# christmas_card.net
KiCad netlist of a schematic drawn in EAGLE
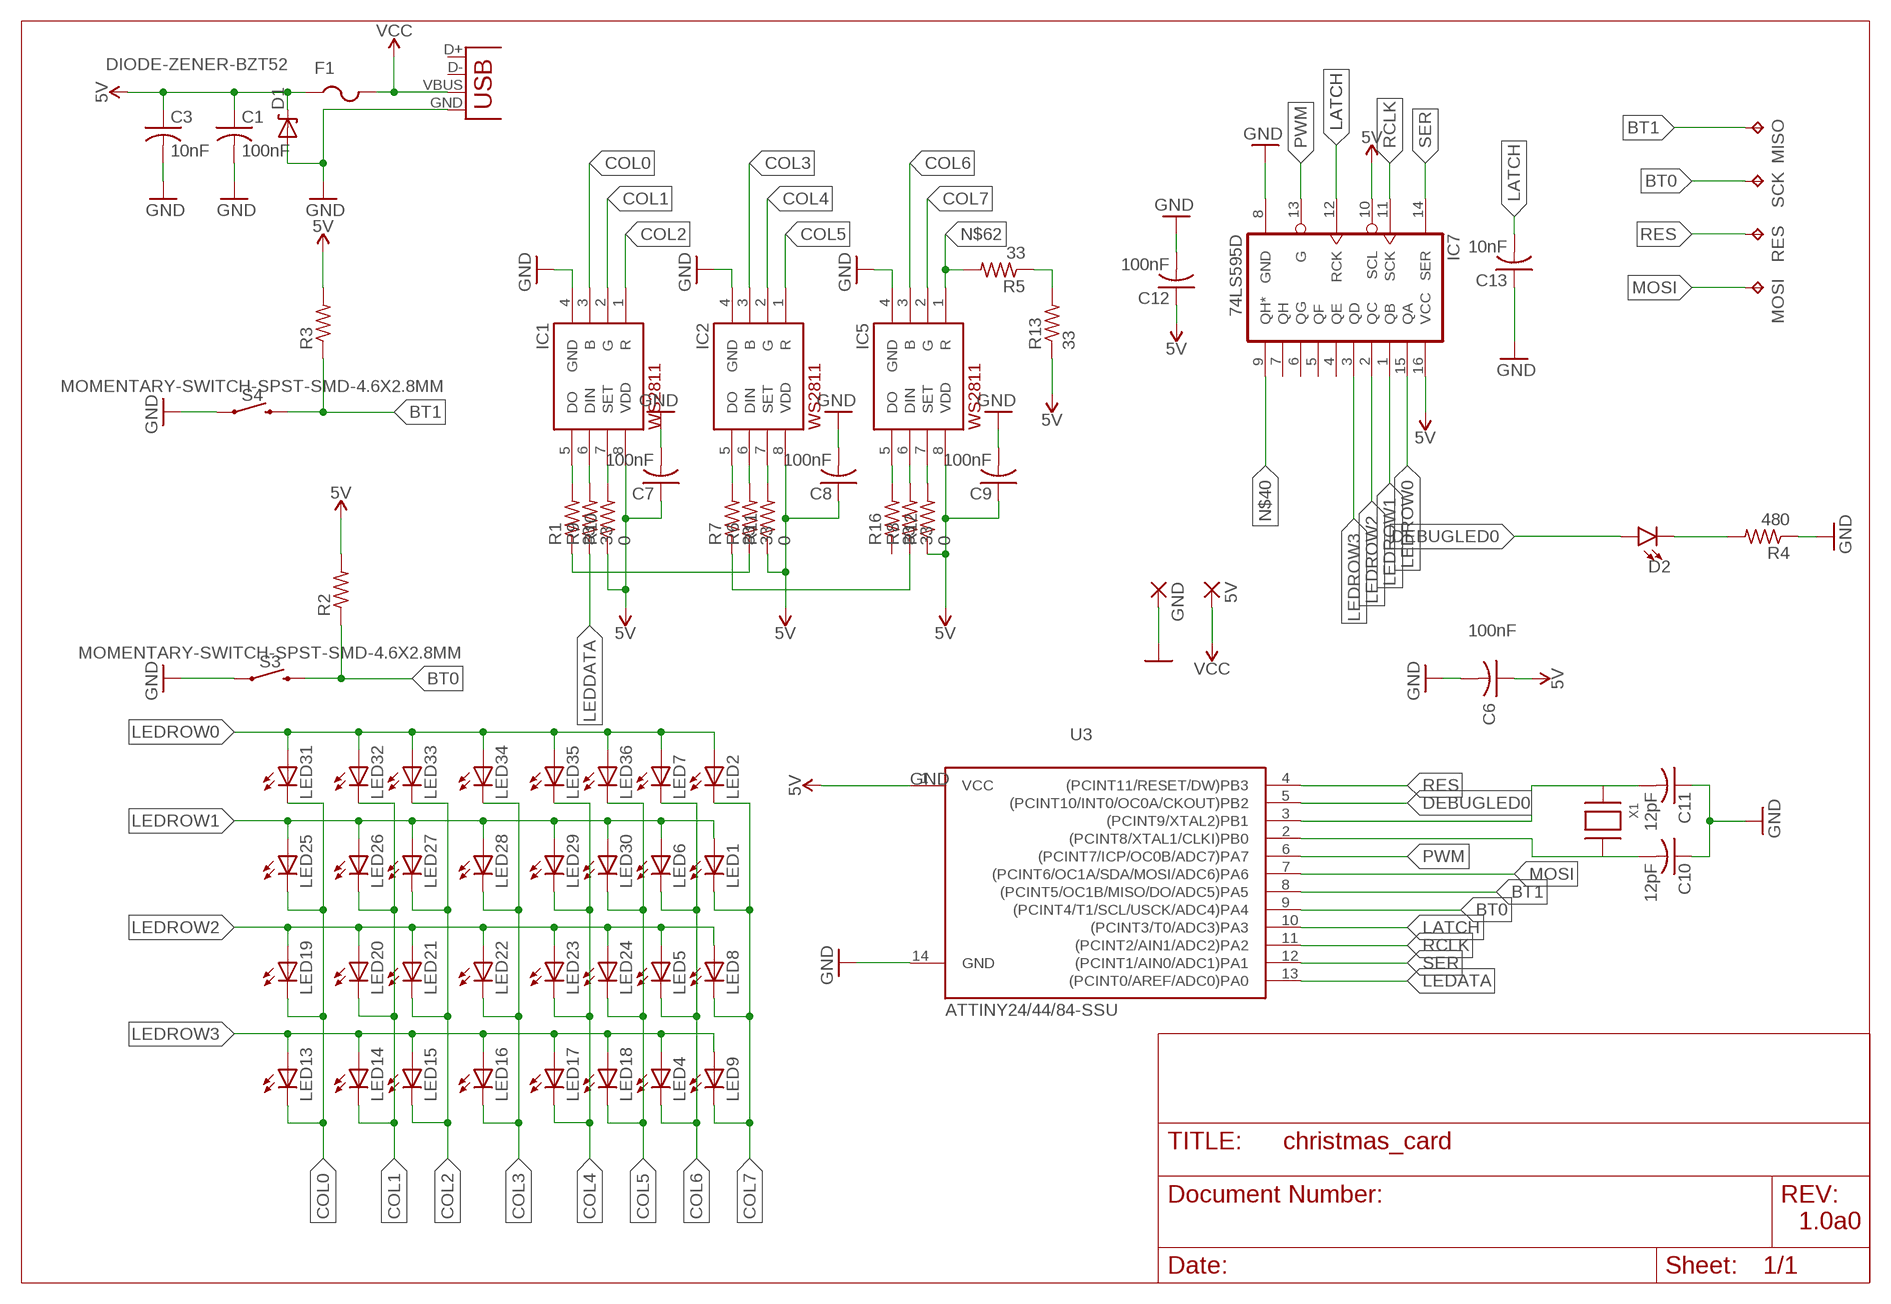
[diagram p0: schematic, sheet 1]

(export (version "E")
  (design (tool "Eeschema 10.0.6"))
  (components
    (comp (ref "5V")
      (value "WIREPADSMD2,54-5,08")
      (footprint "eagle-import:SMD2,54-5,08")
      (libsource (lib "eagle-import") (part "WIREPADSMD2,54-5,08"))
    )
    (comp (ref "C1")
      (value "100nF")
      (footprint "eagle-import:C0603")
      (libsource (lib "eagle-import") (part "C-USC0603"))
    )
    (comp (ref "C3")
      (value "10nF")
      (footprint "eagle-import:C0603")
      (libsource (lib "eagle-import") (part "C-USC0603"))
    )
    (comp (ref "C6")
      (value "100nF")
      (footprint "eagle-import:C0603")
      (libsource (lib "eagle-import") (part "C-USC0603"))
    )
    (comp (ref "C7")
      (value "100nF")
      (footprint "eagle-import:C0603")
      (libsource (lib "eagle-import") (part "C-USC0603"))
    )
    (comp (ref "C8")
      (value "100nF")
      (footprint "eagle-import:C0603")
      (libsource (lib "eagle-import") (part "C-USC0603"))
    )
    (comp (ref "C9")
      (value "100nF")
      (footprint "eagle-import:C0603")
      (libsource (lib "eagle-import") (part "C-USC0603"))
    )
    (comp (ref "C10")
      (value "12pF")
      (footprint "eagle-import:C0603")
      (libsource (lib "eagle-import") (part "C-USC0603"))
    )
    (comp (ref "C11")
      (value "12pF")
      (footprint "eagle-import:C0603")
      (libsource (lib "eagle-import") (part "C-USC0603"))
    )
    (comp (ref "C12")
      (value "100nF")
      (footprint "eagle-import:C0603")
      (libsource (lib "eagle-import") (part "C-USC0603"))
    )
    (comp (ref "C13")
      (value "10nF")
      (footprint "eagle-import:C0603")
      (libsource (lib "eagle-import") (part "C-USC0603"))
    )
    (comp (ref "D1")
      (value "DIODE-ZENER-BZT52")
      (footprint "eagle-import:SOD-323")
      (libsource (lib "eagle-import") (part "DIODE-ZENER-BZT52"))
    )
    (comp (ref "D2")
      (value "LED0603")
      (footprint "eagle-import:LED-0603")
      (libsource (lib "eagle-import") (part "SparkFun-LED_529_LED0603"))
    )
    (comp (ref "F1")
      (value "PTCFUSE-1206")
      (footprint "eagle-import:R1206")
      (libsource (lib "eagle-import") (part "PTCFUSE-1206"))
    )
    (comp (ref "GND")
      (value "WIREPADSMD2,54-5,08")
      (footprint "eagle-import:SMD2,54-5,08")
      (libsource (lib "eagle-import") (part "WIREPADSMD2,54-5,08"))
    )
    (comp (ref "IC1")
      (value "WS2811-SOP8")
      (footprint "eagle-import:SO08-SKINNYPADS")
      (libsource (lib "eagle-import") (part "WS2811-SOP8"))
    )
    (comp (ref "IC2")
      (value "WS2811-SOP8")
      (footprint "eagle-import:SO08-SKINNYPADS")
      (libsource (lib "eagle-import") (part "WS2811-SOP8"))
    )
    (comp (ref "IC5")
      (value "WS2811-SOP8")
      (footprint "eagle-import:SO08-SKINNYPADS")
      (libsource (lib "eagle-import") (part "WS2811-SOP8"))
    )
    (comp (ref "IC7")
      (value "74LS595D")
      (footprint "eagle-import:SO16")
      (fields (field (name "SPICEPREFIX") "X"))
      (libsource (lib "eagle-import") (part "74595DLS"))
    )
    (comp (ref "LED1")
      (value "LED1206")
      (footprint "eagle-import:LED-1206")
      (libsource (lib "eagle-import") (part "LED1206"))
    )
    (comp (ref "LED2")
      (value "LED1206")
      (footprint "eagle-import:LED-1206")
      (libsource (lib "eagle-import") (part "LED1206"))
    )
    (comp (ref "LED4")
      (value "LED1206")
      (footprint "eagle-import:LED-1206")
      (libsource (lib "eagle-import") (part "LED1206"))
    )
    (comp (ref "LED5")
      (value "LED1206")
      (footprint "eagle-import:LED-1206")
      (libsource (lib "eagle-import") (part "LED1206"))
    )
    (comp (ref "LED6")
      (value "LED1206")
      (footprint "eagle-import:LED-1206")
      (libsource (lib "eagle-import") (part "LED1206"))
    )
    (comp (ref "LED7")
      (value "LED1206")
      (footprint "eagle-import:LED-1206")
      (libsource (lib "eagle-import") (part "LED1206"))
    )
    (comp (ref "LED8")
      (value "LED1206")
      (footprint "eagle-import:LED-1206")
      (libsource (lib "eagle-import") (part "LED1206"))
    )
    (comp (ref "LED9")
      (value "LED1206")
      (footprint "eagle-import:LED-1206")
      (libsource (lib "eagle-import") (part "LED1206"))
    )
    (comp (ref "LED13")
      (value "LED1206")
      (footprint "eagle-import:LED-1206")
      (libsource (lib "eagle-import") (part "LED1206"))
    )
    (comp (ref "LED14")
      (value "LED1206")
      (footprint "eagle-import:LED-1206")
      (libsource (lib "eagle-import") (part "LED1206"))
    )
    (comp (ref "LED15")
      (value "LED1206")
      (footprint "eagle-import:LED-1206")
      (libsource (lib "eagle-import") (part "LED1206"))
    )
    (comp (ref "LED16")
      (value "LED1206")
      (footprint "eagle-import:LED-1206")
      (libsource (lib "eagle-import") (part "LED1206"))
    )
    (comp (ref "LED17")
      (value "LED1206")
      (footprint "eagle-import:LED-1206")
      (libsource (lib "eagle-import") (part "LED1206"))
    )
    (comp (ref "LED18")
      (value "LED1206")
      (footprint "eagle-import:LED-1206")
      (libsource (lib "eagle-import") (part "LED1206"))
    )
    (comp (ref "LED19")
      (value "LED1206")
      (footprint "eagle-import:LED-1206")
      (libsource (lib "eagle-import") (part "LED1206"))
    )
    (comp (ref "LED20")
      (value "LED1206")
      (footprint "eagle-import:LED-1206")
      (libsource (lib "eagle-import") (part "LED1206"))
    )
    (comp (ref "LED21")
      (value "LED1206")
      (footprint "eagle-import:LED-1206")
      (libsource (lib "eagle-import") (part "LED1206"))
    )
    (comp (ref "LED22")
      (value "LED1206")
      (footprint "eagle-import:LED-1206")
      (libsource (lib "eagle-import") (part "LED1206"))
    )
    (comp (ref "LED23")
      (value "LED1206")
      (footprint "eagle-import:LED-1206")
      (libsource (lib "eagle-import") (part "LED1206"))
    )
    (comp (ref "LED24")
      (value "LED1206")
      (footprint "eagle-import:LED-1206")
      (libsource (lib "eagle-import") (part "LED1206"))
    )
    (comp (ref "LED25")
      (value "LED1206")
      (footprint "eagle-import:LED-1206")
      (libsource (lib "eagle-import") (part "LED1206"))
    )
    (comp (ref "LED26")
      (value "LED1206")
      (footprint "eagle-import:LED-1206")
      (libsource (lib "eagle-import") (part "LED1206"))
    )
    (comp (ref "LED27")
      (value "LED1206")
      (footprint "eagle-import:LED-1206")
      (libsource (lib "eagle-import") (part "LED1206"))
    )
    (comp (ref "LED28")
      (value "LED1206")
      (footprint "eagle-import:LED-1206")
      (libsource (lib "eagle-import") (part "LED1206"))
    )
    (comp (ref "LED29")
      (value "LED1206")
      (footprint "eagle-import:LED-1206")
      (libsource (lib "eagle-import") (part "LED1206"))
    )
    (comp (ref "LED30")
      (value "LED1206")
      (footprint "eagle-import:LED-1206")
      (libsource (lib "eagle-import") (part "LED1206"))
    )
    (comp (ref "LED31")
      (value "LED1206")
      (footprint "eagle-import:LED-1206")
      (libsource (lib "eagle-import") (part "LED1206"))
    )
    (comp (ref "LED32")
      (value "LED1206")
      (footprint "eagle-import:LED-1206")
      (libsource (lib "eagle-import") (part "LED1206"))
    )
    (comp (ref "LED33")
      (value "LED1206")
      (footprint "eagle-import:LED-1206")
      (libsource (lib "eagle-import") (part "LED1206"))
    )
    (comp (ref "LED34")
      (value "LED1206")
      (footprint "eagle-import:LED-1206")
      (libsource (lib "eagle-import") (part "LED1206"))
    )
    (comp (ref "LED35")
      (value "LED1206")
      (footprint "eagle-import:LED-1206")
      (libsource (lib "eagle-import") (part "LED1206"))
    )
    (comp (ref "LED36")
      (value "LED1206")
      (footprint "eagle-import:LED-1206")
      (libsource (lib "eagle-import") (part "LED1206"))
    )
    (comp (ref "MISO")
      (value "TPB1,27")
      (footprint "eagle-import:B1,27")
      (libsource (lib "eagle-import") (part "TPB1,27"))
    )
    (comp (ref "MOSI")
      (value "TPB1,27")
      (footprint "eagle-import:B1,27")
      (libsource (lib "eagle-import") (part "TPB1,27"))
    )
    (comp (ref "R1")
      (value "33")
      (footprint "eagle-import:R0603")
      (libsource (lib "eagle-import") (part "R-US_R0603"))
    )
    (comp (ref "R2")
      (value "R-US_R0603")
      (footprint "eagle-import:R0603")
      (libsource (lib "eagle-import") (part "R-US_R0603"))
    )
    (comp (ref "R3")
      (value "R-US_R0603")
      (footprint "eagle-import:R0603")
      (libsource (lib "eagle-import") (part "R-US_R0603"))
    )
    (comp (ref "R4")
      (value "480")
      (footprint "eagle-import:R0603")
      (libsource (lib "eagle-import") (part "R-US_R0603"))
    )
    (comp (ref "R5")
      (value "33")
      (footprint "eagle-import:R0603")
      (libsource (lib "eagle-import") (part "R-US_R0603"))
    )
    (comp (ref "R6")
      (value "33")
      (footprint "eagle-import:R0603")
      (libsource (lib "eagle-import") (part "R-US_R0603"))
    )
    (comp (ref "R7")
      (value "33")
      (footprint "eagle-import:R0603")
      (libsource (lib "eagle-import") (part "R-US_R0603"))
    )
    (comp (ref "R8")
      (value "33")
      (footprint "eagle-import:R0603")
      (libsource (lib "eagle-import") (part "R-US_R0603"))
    )
    (comp (ref "R9")
      (value "33")
      (footprint "eagle-import:R0603")
      (libsource (lib "eagle-import") (part "R-US_R0603"))
    )
    (comp (ref "R10")
      (value "0")
      (footprint "eagle-import:R0603")
      (libsource (lib "eagle-import") (part "R-US_R0603"))
    )
    (comp (ref "R11")
      (value "0")
      (footprint "eagle-import:R0603")
      (libsource (lib "eagle-import") (part "R-US_R0603"))
    )
    (comp (ref "R12")
      (value "0")
      (footprint "eagle-import:R0603")
      (libsource (lib "eagle-import") (part "R-US_R0603"))
    )
    (comp (ref "R13")
      (value "33")
      (footprint "eagle-import:R0603")
      (libsource (lib "eagle-import") (part "R-US_R0603"))
    )
    (comp (ref "R16")
      (value "33")
      (footprint "eagle-import:R0603")
      (libsource (lib "eagle-import") (part "R-US_R0603"))
    )
    (comp (ref "RES")
      (value "TPB1,27")
      (footprint "eagle-import:B1,27")
      (libsource (lib "eagle-import") (part "TPB1,27"))
    )
    (comp (ref "S3")
      (value "MOMENTARY-SWITCH-SPST-SMD-4.6X2.8MM")
      (footprint "eagle-import:TACTILE_SWITCH_SMD_4.6X2.8MM")
      (libsource (lib "eagle-import") (part "MOMENTARY-SWITCH-SPST-SMD-4.6X2.8MM"))
    )
    (comp (ref "S4")
      (value "MOMENTARY-SWITCH-SPST-SMD-4.6X2.8MM")
      (footprint "eagle-import:TACTILE_SWITCH_SMD_4.6X2.8MM")
      (libsource (lib "eagle-import") (part "MOMENTARY-SWITCH-SPST-SMD-4.6X2.8MM"))
    )
    (comp (ref "SCK")
      (value "TPB1,27")
      (footprint "eagle-import:B1,27")
      (libsource (lib "eagle-import") (part "TPB1,27"))
    )
    (comp (ref "U3")
      (value "ATTINY24/44/84-SSU")
      (footprint "eagle-import:SOIC14N")
      (libsource (lib "eagle-import") (part "ATTINY24/44/84-SSU"))
    )
    (comp (ref "X1")
      (value "XTALNX5032")
      (footprint "eagle-import:NX5032")
      (libsource (lib "eagle-import") (part "XTALNX5032"))
    )
    (comp (ref "X2")
      (value "USB-MICROB")
      (footprint "eagle-import:USB-MICROB")
      (libsource (lib "eagle-import") (part "USB-MICROB"))
    )
  )
  (nets
    (net (code "1") (name "5V") (class "Default")
      (node (ref "C1") (pin "1") (pinfunction "1_1") (pintype "passive"))
      (node (ref "C12") (pin "1") (pinfunction "1_1") (pintype "passive"))
      (node (ref "C3") (pin "1") (pinfunction "1_1") (pintype "passive"))
      (node (ref "C6") (pin "1") (pinfunction "1_1") (pintype "passive"))
      (node (ref "C7") (pin "1") (pinfunction "1_1") (pintype "passive"))
      (node (ref "C8") (pin "1") (pinfunction "1_1") (pintype "passive"))
      (node (ref "C9") (pin "1") (pinfunction "1_1") (pintype "passive"))
      (node (ref "D1") (pin "1") (pinfunction "C_1") (pintype "passive"))
      (node (ref "F1") (pin "1") (pinfunction "1_1") (pintype "passive"))
      (node (ref "IC1") (pin "8") (pinfunction "VDD_8") (pintype "power_in"))
      (node (ref "IC2") (pin "8") (pinfunction "VDD_8") (pintype "power_in"))
      (node (ref "IC5") (pin "8") (pinfunction "VDD_8") (pintype "power_in"))
      (node (ref "IC7") (pin "10") (pinfunction "SCL_10") (pintype "input"))
      (node (ref "IC7") (pin "16") (pinfunction "VCC_16") (pintype "power_in"))
      (node (ref "R10") (pin "1") (pinfunction "1_1") (pintype "passive"))
      (node (ref "R11") (pin "1") (pinfunction "1_1") (pintype "passive"))
      (node (ref "R12") (pin "1") (pinfunction "1_1") (pintype "passive"))
      (node (ref "R13") (pin "1") (pinfunction "1_1") (pintype "passive"))
      (node (ref "R2") (pin "2") (pinfunction "2_2") (pintype "passive"))
      (node (ref "R3") (pin "2") (pinfunction "2_2") (pintype "passive"))
      (node (ref "U3") (pin "1") (pinfunction "VCC_1") (pintype "bidirectional"))
    )
    (net (code "2") (name "BT0") (class "Default")
      (node (ref "R2") (pin "1") (pinfunction "1_1") (pintype "passive"))
      (node (ref "S3") (pin "3") (pinfunction "2_3") (pintype "passive"))
      (node (ref "S3") (pin "4") (pinfunction "2_4") (pintype "passive"))
      (node (ref "SCK") (pin "TP") (pinfunction "TP_TP") (pintype "input"))
      (node (ref "U3") (pin "9") (pinfunction "(PCINT4/T1/SCL/USCK/ADC4)PA4_9") (pintype "bidirectional"))
    )
    (net (code "3") (name "BT1") (class "Default")
      (node (ref "MISO") (pin "TP") (pinfunction "TP_TP") (pintype "input"))
      (node (ref "R3") (pin "1") (pinfunction "1_1") (pintype "passive"))
      (node (ref "S4") (pin "3") (pinfunction "2_3") (pintype "passive"))
      (node (ref "S4") (pin "4") (pinfunction "2_4") (pintype "passive"))
      (node (ref "U3") (pin "8") (pinfunction "(PCINT5/OC1B/MISO/DO/ADC5)PA5_8") (pintype "bidirectional"))
    )
    (net (code "4") (name "COL0") (class "Default")
      (node (ref "IC1") (pin "3") (pinfunction "B_3") (pintype "open_collector"))
      (node (ref "LED13") (pin "C") (pinfunction "C_C") (pintype "passive"))
      (node (ref "LED19") (pin "C") (pinfunction "C_C") (pintype "passive"))
      (node (ref "LED25") (pin "C") (pinfunction "C_C") (pintype "passive"))
      (node (ref "LED31") (pin "C") (pinfunction "C_C") (pintype "passive"))
    )
    (net (code "5") (name "COL1") (class "Default")
      (node (ref "IC1") (pin "2") (pinfunction "G_2") (pintype "open_collector"))
      (node (ref "LED14") (pin "C") (pinfunction "C_C") (pintype "passive"))
      (node (ref "LED20") (pin "C") (pinfunction "C_C") (pintype "passive"))
      (node (ref "LED26") (pin "C") (pinfunction "C_C") (pintype "passive"))
      (node (ref "LED32") (pin "C") (pinfunction "C_C") (pintype "passive"))
    )
    (net (code "6") (name "COL2") (class "Default")
      (node (ref "IC1") (pin "1") (pinfunction "R_1") (pintype "open_collector"))
      (node (ref "LED15") (pin "C") (pinfunction "C_C") (pintype "passive"))
      (node (ref "LED21") (pin "C") (pinfunction "C_C") (pintype "passive"))
      (node (ref "LED27") (pin "C") (pinfunction "C_C") (pintype "passive"))
      (node (ref "LED33") (pin "C") (pinfunction "C_C") (pintype "passive"))
    )
    (net (code "7") (name "COL3") (class "Default")
      (node (ref "IC2") (pin "3") (pinfunction "B_3") (pintype "open_collector"))
      (node (ref "LED16") (pin "C") (pinfunction "C_C") (pintype "passive"))
      (node (ref "LED22") (pin "C") (pinfunction "C_C") (pintype "passive"))
      (node (ref "LED28") (pin "C") (pinfunction "C_C") (pintype "passive"))
      (node (ref "LED34") (pin "C") (pinfunction "C_C") (pintype "passive"))
    )
    (net (code "8") (name "COL4") (class "Default")
      (node (ref "IC2") (pin "2") (pinfunction "G_2") (pintype "open_collector"))
      (node (ref "LED17") (pin "C") (pinfunction "C_C") (pintype "passive"))
      (node (ref "LED23") (pin "C") (pinfunction "C_C") (pintype "passive"))
      (node (ref "LED29") (pin "C") (pinfunction "C_C") (pintype "passive"))
      (node (ref "LED35") (pin "C") (pinfunction "C_C") (pintype "passive"))
    )
    (net (code "9") (name "COL5") (class "Default")
      (node (ref "IC2") (pin "1") (pinfunction "R_1") (pintype "open_collector"))
      (node (ref "LED18") (pin "C") (pinfunction "C_C") (pintype "passive"))
      (node (ref "LED24") (pin "C") (pinfunction "C_C") (pintype "passive"))
      (node (ref "LED30") (pin "C") (pinfunction "C_C") (pintype "passive"))
      (node (ref "LED36") (pin "C") (pinfunction "C_C") (pintype "passive"))
    )
    (net (code "10") (name "COL6") (class "Default")
      (node (ref "IC5") (pin "3") (pinfunction "B_3") (pintype "open_collector"))
      (node (ref "LED4") (pin "C") (pinfunction "C_C") (pintype "passive"))
      (node (ref "LED5") (pin "C") (pinfunction "C_C") (pintype "passive"))
      (node (ref "LED6") (pin "C") (pinfunction "C_C") (pintype "passive"))
      (node (ref "LED7") (pin "C") (pinfunction "C_C") (pintype "passive"))
    )
    (net (code "11") (name "COL7") (class "Default")
      (node (ref "IC5") (pin "2") (pinfunction "G_2") (pintype "open_collector"))
      (node (ref "LED1") (pin "C") (pinfunction "C_C") (pintype "passive"))
      (node (ref "LED2") (pin "C") (pinfunction "C_C") (pintype "passive"))
      (node (ref "LED8") (pin "C") (pinfunction "C_C") (pintype "passive"))
      (node (ref "LED9") (pin "C") (pinfunction "C_C") (pintype "passive"))
    )
    (net (code "12") (name "DEBUGLED0") (class "Default")
      (node (ref "D2") (pin "A") (pinfunction "A_A") (pintype "passive"))
      (node (ref "U3") (pin "5") (pinfunction "(PCINT10/INT0/OC0A/CKOUT)PB2_5") (pintype "bidirectional"))
    )
    (net (code "13") (name "GND") (class "Default")
      (node (ref "C1") (pin "2") (pinfunction "2_2") (pintype "passive"))
      (node (ref "C10") (pin "1") (pinfunction "1_1") (pintype "passive"))
      (node (ref "C11") (pin "1") (pinfunction "1_1") (pintype "passive"))
      (node (ref "C12") (pin "2") (pinfunction "2_2") (pintype "passive"))
      (node (ref "C13") (pin "1") (pinfunction "1_1") (pintype "passive"))
      (node (ref "C3") (pin "2") (pinfunction "2_2") (pintype "passive"))
      (node (ref "C6") (pin "2") (pinfunction "2_2") (pintype "passive"))
      (node (ref "C7") (pin "2") (pinfunction "2_2") (pintype "passive"))
      (node (ref "C8") (pin "2") (pinfunction "2_2") (pintype "passive"))
      (node (ref "C9") (pin "2") (pinfunction "2_2") (pintype "passive"))
      (node (ref "D1") (pin "2") (pinfunction "A_2") (pintype "passive"))
      (node (ref "GND") (pin "1") (pinfunction "P_1") (pintype "passive"))
      (node (ref "IC1") (pin "4") (pinfunction "GND_4") (pintype "power_in"))
      (node (ref "IC2") (pin "4") (pinfunction "GND_4") (pintype "power_in"))
      (node (ref "IC5") (pin "4") (pinfunction "GND_4") (pintype "power_in"))
      (node (ref "IC7") (pin "8") (pinfunction "GND_8") (pintype "power_in"))
      (node (ref "R4") (pin "1") (pinfunction "1_1") (pintype "passive"))
      (node (ref "S3") (pin "1") (pinfunction "1_1") (pintype "passive"))
      (node (ref "S3") (pin "2") (pinfunction "1_2") (pintype "passive"))
      (node (ref "S4") (pin "1") (pinfunction "1_1") (pintype "passive"))
      (node (ref "S4") (pin "2") (pinfunction "1_2") (pintype "passive"))
      (node (ref "U3") (pin "14") (pinfunction "GND_14") (pintype "bidirectional"))
      (node (ref "X2") (pin "GND") (pinfunction "GND_GND") (pintype "bidirectional"))
    )
    (net (code "14") (name "LATCH") (class "Default")
      (node (ref "C13") (pin "2") (pinfunction "2_2") (pintype "passive"))
      (node (ref "IC7") (pin "12") (pinfunction "RCK_12") (pintype "input"))
      (node (ref "U3") (pin "10") (pinfunction "(PCINT3/T0/ADC3)PA3_10") (pintype "bidirectional"))
    )
    (net (code "15") (name "LEDATA") (class "Default")
      (node (ref "U3") (pin "13") (pinfunction "(PCINT0/AREF/ADC0)PA0_13") (pintype "bidirectional"))
    )
    (net (code "16") (name "LEDDATA") (class "Default")
      (node (ref "R9") (pin "1") (pinfunction "1_1") (pintype "passive"))
    )
    (net (code "17") (name "LEDROW0") (class "Default")
      (node (ref "IC7") (pin "15") (pinfunction "QA_15") (pintype "tri_state"))
      (node (ref "LED2") (pin "A") (pinfunction "A_A") (pintype "passive"))
      (node (ref "LED31") (pin "A") (pinfunction "A_A") (pintype "passive"))
      (node (ref "LED32") (pin "A") (pinfunction "A_A") (pintype "passive"))
      (node (ref "LED33") (pin "A") (pinfunction "A_A") (pintype "passive"))
      (node (ref "LED34") (pin "A") (pinfunction "A_A") (pintype "passive"))
      (node (ref "LED35") (pin "A") (pinfunction "A_A") (pintype "passive"))
      (node (ref "LED36") (pin "A") (pinfunction "A_A") (pintype "passive"))
      (node (ref "LED7") (pin "A") (pinfunction "A_A") (pintype "passive"))
    )
    (net (code "18") (name "LEDROW1") (class "Default")
      (node (ref "IC7") (pin "1") (pinfunction "QB_1") (pintype "tri_state"))
      (node (ref "LED1") (pin "A") (pinfunction "A_A") (pintype "passive"))
      (node (ref "LED25") (pin "A") (pinfunction "A_A") (pintype "passive"))
      (node (ref "LED26") (pin "A") (pinfunction "A_A") (pintype "passive"))
      (node (ref "LED27") (pin "A") (pinfunction "A_A") (pintype "passive"))
      (node (ref "LED28") (pin "A") (pinfunction "A_A") (pintype "passive"))
      (node (ref "LED29") (pin "A") (pinfunction "A_A") (pintype "passive"))
      (node (ref "LED30") (pin "A") (pinfunction "A_A") (pintype "passive"))
      (node (ref "LED6") (pin "A") (pinfunction "A_A") (pintype "passive"))
    )
    (net (code "19") (name "LEDROW2") (class "Default")
      (node (ref "IC7") (pin "2") (pinfunction "QC_2") (pintype "tri_state"))
      (node (ref "LED19") (pin "A") (pinfunction "A_A") (pintype "passive"))
      (node (ref "LED20") (pin "A") (pinfunction "A_A") (pintype "passive"))
      (node (ref "LED21") (pin "A") (pinfunction "A_A") (pintype "passive"))
      (node (ref "LED22") (pin "A") (pinfunction "A_A") (pintype "passive"))
      (node (ref "LED23") (pin "A") (pinfunction "A_A") (pintype "passive"))
      (node (ref "LED24") (pin "A") (pinfunction "A_A") (pintype "passive"))
      (node (ref "LED5") (pin "A") (pinfunction "A_A") (pintype "passive"))
      (node (ref "LED8") (pin "A") (pinfunction "A_A") (pintype "passive"))
    )
    (net (code "20") (name "LEDROW3") (class "Default")
      (node (ref "IC7") (pin "3") (pinfunction "QD_3") (pintype "tri_state"))
      (node (ref "LED13") (pin "A") (pinfunction "A_A") (pintype "passive"))
      (node (ref "LED14") (pin "A") (pinfunction "A_A") (pintype "passive"))
      (node (ref "LED15") (pin "A") (pinfunction "A_A") (pintype "passive"))
      (node (ref "LED16") (pin "A") (pinfunction "A_A") (pintype "passive"))
      (node (ref "LED17") (pin "A") (pinfunction "A_A") (pintype "passive"))
      (node (ref "LED18") (pin "A") (pinfunction "A_A") (pintype "passive"))
      (node (ref "LED4") (pin "A") (pinfunction "A_A") (pintype "passive"))
      (node (ref "LED9") (pin "A") (pinfunction "A_A") (pintype "passive"))
    )
    (net (code "21") (name "MOSI") (class "Default")
      (node (ref "MOSI") (pin "TP") (pinfunction "TP_TP") (pintype "input"))
      (node (ref "U3") (pin "7") (pinfunction "(PCINT6/OC1A/SDA/MOSI/ADC6)PA6_7") (pintype "bidirectional"))
    )
    (net (code "22") (name "N$40") (class "Default")
      (node (ref "IC7") (pin "9") (pinfunction "QH*_9") (pintype "tri_state"))
    )
    (net (code "23") (name "N$62") (class "Default")
      (node (ref "IC5") (pin "1") (pinfunction "R_1") (pintype "open_collector"))
      (node (ref "R5") (pin "2") (pinfunction "2_2") (pintype "passive"))
    )
    (net (code "24") (name "Net-(D2-PadC)") (class "Default")
      (node (ref "D2") (pin "C") (pinfunction "C_C") (pintype "passive"))
      (node (ref "R4") (pin "2") (pinfunction "2_2") (pintype "passive"))
    )
    (net (code "25") (name "Net-(IC1-DIN)") (class "Default")
      (node (ref "IC1") (pin "6") (pinfunction "DIN_6") (pintype "input"))
      (node (ref "R9") (pin "2") (pinfunction "2_2") (pintype "passive"))
    )
    (net (code "26") (name "Net-(IC1-DO)") (class "Default")
      (node (ref "IC1") (pin "5") (pinfunction "DO_5") (pintype "output"))
      (node (ref "R1") (pin "2") (pinfunction "2_2") (pintype "passive"))
    )
    (net (code "27") (name "Net-(IC1-SET)") (class "Default")
      (node (ref "IC1") (pin "7") (pinfunction "SET_7") (pintype "input"))
      (node (ref "R10") (pin "2") (pinfunction "2_2") (pintype "passive"))
    )
    (net (code "28") (name "Net-(IC2-DIN)") (class "Default")
      (node (ref "IC2") (pin "6") (pinfunction "DIN_6") (pintype "input"))
      (node (ref "R6") (pin "2") (pinfunction "2_2") (pintype "passive"))
    )
    (net (code "29") (name "Net-(IC2-DO)") (class "Default")
      (node (ref "IC2") (pin "5") (pinfunction "DO_5") (pintype "output"))
      (node (ref "R7") (pin "2") (pinfunction "2_2") (pintype "passive"))
    )
    (net (code "30") (name "Net-(IC2-SET)") (class "Default")
      (node (ref "IC2") (pin "7") (pinfunction "SET_7") (pintype "input"))
      (node (ref "R11") (pin "2") (pinfunction "2_2") (pintype "passive"))
    )
    (net (code "31") (name "Net-(IC5-DIN)") (class "Default")
      (node (ref "IC5") (pin "6") (pinfunction "DIN_6") (pintype "input"))
      (node (ref "R8") (pin "2") (pinfunction "2_2") (pintype "passive"))
    )
    (net (code "32") (name "Net-(IC5-DO)") (class "Default")
      (node (ref "IC5") (pin "5") (pinfunction "DO_5") (pintype "output"))
      (node (ref "R16") (pin "2") (pinfunction "2_2") (pintype "passive"))
    )
    (net (code "33") (name "Net-(IC5-SET)") (class "Default")
      (node (ref "IC5") (pin "7") (pinfunction "SET_7") (pintype "input"))
      (node (ref "R12") (pin "2") (pinfunction "2_2") (pintype "passive"))
    )
    (net (code "34") (name "Net-(R1-Pad1)") (class "Default")
      (node (ref "R1") (pin "1") (pinfunction "1_1") (pintype "passive"))
      (node (ref "R6") (pin "1") (pinfunction "1_1") (pintype "passive"))
    )
    (net (code "35") (name "Net-(R7-Pad1)") (class "Default")
      (node (ref "R7") (pin "1") (pinfunction "1_1") (pintype "passive"))
      (node (ref "R8") (pin "1") (pinfunction "1_1") (pintype "passive"))
    )
    (net (code "36") (name "Net-(R13-Pad2)") (class "Default")
      (node (ref "R13") (pin "2") (pinfunction "2_2") (pintype "passive"))
      (node (ref "R5") (pin "1") (pinfunction "1_1") (pintype "passive"))
    )
    (net (code "37") (name "Net-(U3-(PCINT8{slash}XTAL1{slash}CLKI)PB0)") (class "Default")
      (node (ref "C10") (pin "2") (pinfunction "2_2") (pintype "passive"))
      (node (ref "U3") (pin "2") (pinfunction "(PCINT8/XTAL1/CLKI)PB0_2") (pintype "bidirectional"))
      (node (ref "X1") (pin "P$2") (pinfunction "P$2_P$2") (pintype "bidirectional"))
    )
    (net (code "38") (name "Net-(U3-(PCINT9{slash}XTAL2)PB1)") (class "Default")
      (node (ref "C11") (pin "2") (pinfunction "2_2") (pintype "passive"))
      (node (ref "U3") (pin "3") (pinfunction "(PCINT9/XTAL2)PB1_3") (pintype "bidirectional"))
      (node (ref "X1") (pin "P$1") (pinfunction "P$1_P$1") (pintype "bidirectional"))
    )
    (net (code "39") (name "PWM") (class "Default")
      (node (ref "IC7") (pin "13") (pinfunction "G_13") (pintype "input"))
      (node (ref "U3") (pin "6") (pinfunction "(PCINT7/ICP/OC0B/ADC7)PA7_6") (pintype "bidirectional"))
    )
    (net (code "40") (name "RCLK") (class "Default")
      (node (ref "IC7") (pin "11") (pinfunction "SCK_11") (pintype "input"))
      (node (ref "U3") (pin "11") (pinfunction "(PCINT2/AIN1/ADC2)PA2_11") (pintype "bidirectional"))
    )
    (net (code "41") (name "RES") (class "Default")
      (node (ref "RES") (pin "TP") (pinfunction "TP_TP") (pintype "input"))
      (node (ref "U3") (pin "4") (pinfunction "(PCINT11/RESET/DW)PB3_4") (pintype "bidirectional"))
    )
    (net (code "42") (name "SER") (class "Default")
      (node (ref "IC7") (pin "14") (pinfunction "SER_14") (pintype "input"))
      (node (ref "U3") (pin "12") (pinfunction "(PCINT1/AIN0/ADC1)PA1_12") (pintype "bidirectional"))
    )
    (net (code "43") (name "VCC") (class "Default")
      (node (ref "5V") (pin "1") (pinfunction "P_1") (pintype "passive"))
      (node (ref "F1") (pin "2") (pinfunction "2_2") (pintype "passive"))
      (node (ref "X2") (pin "VBUS") (pinfunction "VBUS_VBUS") (pintype "bidirectional"))
    )
    (net (code "44") (name "unconnected-(IC7-QE-Pad4)") (class "Default")
      (node (ref "IC7") (pin "4") (pinfunction "QE_4") (pintype "tri_state"))
    )
    (net (code "45") (name "unconnected-(IC7-QF-Pad5)") (class "Default")
      (node (ref "IC7") (pin "5") (pinfunction "QF_5") (pintype "tri_state"))
    )
    (net (code "46") (name "unconnected-(IC7-QG-Pad6)") (class "Default")
      (node (ref "IC7") (pin "6") (pinfunction "QG_6") (pintype "tri_state"))
    )
    (net (code "47") (name "unconnected-(IC7-QH-Pad7)") (class "Default")
      (node (ref "IC7") (pin "7") (pinfunction "QH_7") (pintype "tri_state"))
    )
    (net (code "48") (name "unconnected-(R16-Pad1)") (class "Default")
      (node (ref "R16") (pin "1") (pinfunction "1_1") (pintype "passive"))
    )
    (net (code "49") (name "unconnected-(X2-PadD+)") (class "Default")
      (node (ref "X2") (pin "D+") (pinfunction "D+_D+") (pintype "bidirectional"))
    )
    (net (code "50") (name "unconnected-(X2-PadD-)") (class "Default")
      (node (ref "X2") (pin "D-") (pinfunction "D-_D-") (pintype "bidirectional"))
    )
  )
)
